# MachLoa.net
KiCad netlist of a schematic drawn in Altium Designer
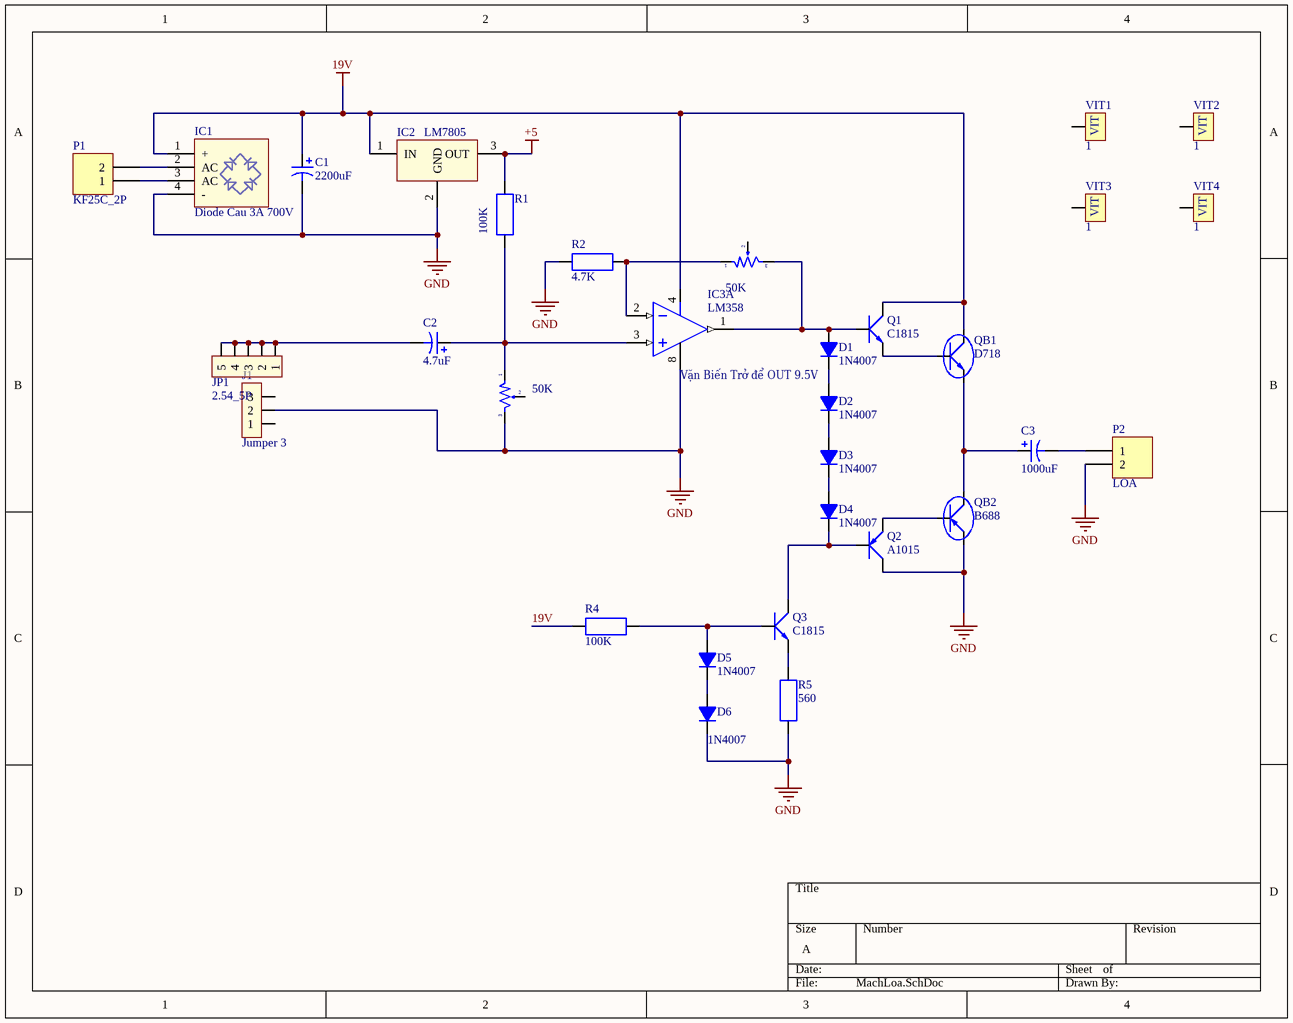
[diagram p0: MachLoa.SchDoc]

(export (version "E")
  (design (tool "Eeschema 10.0.6"))
  (components
    (comp (ref "C1")
      (value "2200uF")
      (footprint "C10mm")
      (description "Polarized Capacitor (Axial)")
      (fields (field (name "PUBLISHER") "Altium Limited"))
      (libsource (lib "NBBLib 14-03-2012") (part "Cap Pol 12mm"))
    )
    (comp (ref "C2")
      (value "4.7uF")
      (footprint "C10mm")
      (description "Polarized Capacitor (Axial)")
      (fields (field (name "PUBLISHER") "Altium Limited"))
      (libsource (lib "NBBLib 14-03-2012") (part "Cap Pol 12mm"))
    )
    (comp (ref "C3")
      (value "1000uF")
      (footprint "C10mm")
      (description "Polarized Capacitor (Axial)")
      (fields (field (name "PUBLISHER") "Altium Limited"))
      (libsource (lib "NBBLib 14-03-2012") (part "Cap Pol 12mm"))
    )
    (comp (ref "D1")
      (value "1N4007")
      (footprint "D1A")
      (description "Diode 1A")
      (libsource (lib "syhaunguyen") (part "D1A"))
    )
    (comp (ref "D2")
      (value "1N4007")
      (footprint "D1A")
      (description "Diode 1A")
      (libsource (lib "syhaunguyen") (part "D1A"))
    )
    (comp (ref "D3")
      (value "1N4007")
      (footprint "D1A")
      (description "Diode 1A")
      (libsource (lib "syhaunguyen") (part "D1A"))
    )
    (comp (ref "D4")
      (value "1N4007")
      (footprint "D1A")
      (description "Diode 1A")
      (libsource (lib "syhaunguyen") (part "D1A"))
    )
    (comp (ref "D5")
      (value "1N4007")
      (footprint "D1A")
      (description "Diode 1A")
      (libsource (lib "syhaunguyen") (part "D1A"))
    )
    (comp (ref "D6")
      (value "1N4007")
      (footprint "D1A")
      (description "Diode 1A")
      (libsource (lib "syhaunguyen") (part "D1A"))
    )
    (comp (ref "IC1")
      (value "Diode Cau 3A 700V")
      (footprint "diode cau")
      (description "Cắm")
      (libsource (lib "SCH Chuan") (part "Diode Cau 3A 700V"))
    )
    (comp (ref "IC2")
      (value "LM7805")
      (footprint "QTO-220H3")
      (description "On ap +, from + 5 to + 24VDC")
      (libsource (lib "syhaunguyen") (part "LM78xx"))
    )
    (comp (ref "IC3")
      (value "LM358")
      (footprint "DIP8/W0.3")
      (description "Low-Power Dual Operational Amplifier")
      (libsource (lib "syhaunguyen") (part "LM358"))
    )
    (comp (ref "J1") (value "Jumper 3") (footprint "JP3") (libsource (lib "syhaunguyen") (part "JP3")))
    (comp (ref "JP1")
      (value "2.54_5P")
      (footprint "jump don duc 2.54_5p")
      (description "Cắm")
      (libsource (lib "NhomLib") (part "Jump Don Duc 2.54_5P"))
    )
    (comp (ref "P1")
      (value "KF25C_2P")
      (footprint "KF25C_2P")
      (description "Header, 2-Pin, pitch 7.62mm")
      (libsource (lib "") (part "KF25C_2P_1"))
    )
    (comp (ref "P2")
      (value "LOA")
      (footprint "KF25C_2P")
      (description "Header, 2-Pin, pitch 7.62mm")
      (fields (field (name "MPN") "KF25C_2P"))
      (libsource (lib "BYTECH_HW_LIB_2019") (part "KF25C_2P"))
    )
    (comp (ref "Q1")
      (value "C1815")
      (footprint "QTO-92")
      (description "NPN 600mW, ECB")
      (libsource (lib "syhaunguyen") (part "C1815"))
    )
    (comp (ref "Q2")
      (value "A1015")
      (footprint "QTO-92")
      (description "PNP 600mW, ECB")
      (libsource (lib "syhaunguyen") (part "A1015"))
    )
    (comp (ref "Q3")
      (value "C1815")
      (footprint "QTO-92")
      (description "NPN 600mW, ECB")
      (libsource (lib "syhaunguyen") (part "C1815"))
    )
    (comp (ref "QB1")
      (value "D718")
      (footprint "QTO-247")
      (description "Transistor Power Supply")
      (libsource (lib "syhaunguyen") (part "D718"))
    )
    (comp (ref "QB2")
      (value "B688")
      (footprint "QTO-247")
      (description "Transistor Power Supply")
      (libsource (lib "syhaunguyen") (part "B688"))
    )
    (comp (ref "R1")
      (value "100K")
      (footprint "R2W")
      (description "Resistor 2W")
      (libsource (lib "syhaunguyen") (part "R2W"))
    )
    (comp (ref "R2")
      (value "4.7K")
      (footprint "R2W")
      (description "Resistor 2W")
      (libsource (lib "syhaunguyen") (part "R2W"))
    )
    (comp (ref "R4")
      (value "100K")
      (footprint "R2W")
      (description "Resistor 2W")
      (libsource (lib "syhaunguyen") (part "R2W"))
    )
    (comp (ref "R5")
      (value "560")
      (footprint "R2W")
      (description "Resistor 2W")
      (libsource (lib "syhaunguyen") (part "R2W"))
    )
    (comp (ref "VIT1")
      (value "1")
      (footprint "VIT")
      (description "Oc Vit")
      (libsource (lib "syhaunguyen") (part "VIT"))
    )
    (comp (ref "VIT2")
      (value "1")
      (footprint "VIT")
      (description "Oc Vit")
      (libsource (lib "syhaunguyen") (part "VIT"))
    )
    (comp (ref "VIT3")
      (value "1")
      (footprint "VIT")
      (description "Oc Vit")
      (libsource (lib "syhaunguyen") (part "VIT"))
    )
    (comp (ref "VIT4")
      (value "1")
      (footprint "VIT")
      (description "Oc Vit")
      (libsource (lib "syhaunguyen") (part "VIT"))
    )
    (comp (ref "Volum1")
      (value "50K")
      (footprint "BIEN TRO VI CHINH Dung")
      (description "Volume control Dual")
      (libsource (lib "syhaunguyen") (part "VOL-D"))
    )
    (comp (ref "Volum2")
      (value "50K")
      (footprint "VOL-D")
      (description "Volume control Dual")
      (libsource (lib "syhaunguyen") (part "VOL-D"))
    )
  )
  (nets
    (net (code "1") (name "+5") (class "Default")
      (node (ref "IC2") (pin "3") (pinfunction "OUT_3") (pintype "passive"))
      (node (ref "R1") (pin "2") (pinfunction "2_2") (pintype "passive"))
    )
    (net (code "2") (name "19V") (class "Default")
      (node (ref "C1") (pin "1") (pinfunction "1_1") (pintype "passive"))
      (node (ref "IC1") (pin "1") (pinfunction "+_1") (pintype "passive"))
      (node (ref "IC2") (pin "1") (pinfunction "IN_1") (pintype "passive"))
      (node (ref "IC3") (pin "4") (pinfunction "-V_4") (pintype "passive"))
      (node (ref "Q1") (pin "2") (pinfunction "C_2") (pintype "passive"))
      (node (ref "QB1") (pin "2") (pinfunction "C_2") (pintype "passive"))
      (node (ref "R4") (pin "2") (pinfunction "2_2") (pintype "passive"))
    )
    (net (code "3") (name "GND") (class "Default")
      (node (ref "C1") (pin "2") (pinfunction "2_2") (pintype "passive"))
      (node (ref "D6") (pin "2") (pinfunction "K_2") (pintype "passive"))
      (node (ref "IC1") (pin "4") (pinfunction "-_4") (pintype "passive"))
      (node (ref "IC2") (pin "2") (pinfunction "GND_2") (pintype "passive"))
      (node (ref "IC3") (pin "8") (pinfunction "+V_8") (pintype "passive"))
      (node (ref "J1") (pin "2") (pinfunction "2_2") (pintype "passive"))
      (node (ref "P2") (pin "2") (pinfunction "2_2") (pintype "passive"))
      (node (ref "Q2") (pin "2") (pinfunction "C_2") (pintype "passive"))
      (node (ref "QB2") (pin "3") (pinfunction "E_3") (pintype "passive"))
      (node (ref "R2") (pin "2") (pinfunction "2_2") (pintype "passive"))
      (node (ref "R5") (pin "2") (pinfunction "2_2") (pintype "passive"))
      (node (ref "Volum1") (pin "3") (pinfunction "3_3") (pintype "passive"))
    )
    (net (code "4") (name "Net-(C2-Pad2)") (class "Default")
      (node (ref "C2") (pin "2") (pinfunction "2_2") (pintype "passive"))
      (node (ref "JP1") (pin "1") (pinfunction "1_1") (pintype "passive"))
      (node (ref "JP1") (pin "2") (pinfunction "2_2") (pintype "passive"))
      (node (ref "JP1") (pin "3") (pinfunction "3_3") (pintype "passive"))
      (node (ref "JP1") (pin "4") (pinfunction "4_4") (pintype "passive"))
      (node (ref "JP1") (pin "5") (pinfunction "5_5") (pintype "passive"))
    )
    (net (code "5") (name "Net-(C3-Pad2)") (class "Default")
      (node (ref "C3") (pin "2") (pinfunction "2_2") (pintype "passive"))
      (node (ref "P2") (pin "1") (pinfunction "1_1") (pintype "passive"))
    )
    (net (code "6") (name "Net-(D1-A)") (class "Default")
      (node (ref "D1") (pin "1") (pinfunction "A_1") (pintype "passive"))
      (node (ref "IC3") (pin "1") (pinfunction "OUT_1") (pintype "output"))
      (node (ref "Q1") (pin "3") (pinfunction "B_3") (pintype "passive"))
      (node (ref "Volum2") (pin "3") (pinfunction "3_3") (pintype "passive"))
    )
    (net (code "7") (name "Net-(D1-K)") (class "Default")
      (node (ref "D1") (pin "2") (pinfunction "K_2") (pintype "passive"))
      (node (ref "D2") (pin "1") (pinfunction "A_1") (pintype "passive"))
    )
    (net (code "8") (name "Net-(D2-K)") (class "Default")
      (node (ref "D2") (pin "2") (pinfunction "K_2") (pintype "passive"))
      (node (ref "D3") (pin "1") (pinfunction "A_1") (pintype "passive"))
    )
    (net (code "9") (name "Net-(D3-K)") (class "Default")
      (node (ref "D3") (pin "2") (pinfunction "K_2") (pintype "passive"))
      (node (ref "D4") (pin "1") (pinfunction "A_1") (pintype "passive"))
    )
    (net (code "10") (name "Net-(D4-K)") (class "Default")
      (node (ref "D4") (pin "2") (pinfunction "K_2") (pintype "passive"))
      (node (ref "Q2") (pin "3") (pinfunction "B_3") (pintype "passive"))
      (node (ref "Q3") (pin "2") (pinfunction "C_2") (pintype "passive"))
    )
    (net (code "11") (name "Net-(D5-A)") (class "Default")
      (node (ref "D5") (pin "1") (pinfunction "A_1") (pintype "passive"))
      (node (ref "Q3") (pin "3") (pinfunction "B_3") (pintype "passive"))
      (node (ref "R4") (pin "1") (pinfunction "1_1") (pintype "passive"))
    )
    (net (code "12") (name "Net-(D5-K)") (class "Default")
      (node (ref "D5") (pin "2") (pinfunction "K_2") (pintype "passive"))
      (node (ref "D6") (pin "1") (pinfunction "A_1") (pintype "passive"))
    )
    (net (code "13") (name "Net-(IC1-AC-Pad2)") (class "Default")
      (node (ref "IC1") (pin "2") (pinfunction "AC_2") (pintype "passive"))
      (node (ref "P1") (pin "2") (pinfunction "2_2") (pintype "passive"))
    )
    (net (code "14") (name "Net-(IC1-AC-Pad3)") (class "Default")
      (node (ref "IC1") (pin "3") (pinfunction "AC_3") (pintype "passive"))
      (node (ref "P1") (pin "1") (pinfunction "1_1") (pintype "passive"))
    )
    (net (code "15") (name "Net-(IC3A-IN+)") (class "Default")
      (node (ref "C2") (pin "1") (pinfunction "1_1") (pintype "passive"))
      (node (ref "IC3") (pin "3") (pinfunction "IN+_3") (pintype "input"))
      (node (ref "R1") (pin "1") (pinfunction "1_1") (pintype "passive"))
      (node (ref "Volum1") (pin "1") (pinfunction "1_1") (pintype "passive"))
    )
    (net (code "16") (name "Net-(IC3A-IN-)") (class "Default")
      (node (ref "IC3") (pin "2") (pinfunction "IN-_2") (pintype "input"))
      (node (ref "R2") (pin "1") (pinfunction "1_1") (pintype "passive"))
      (node (ref "Volum2") (pin "1") (pinfunction "1_1") (pintype "passive"))
    )
    (net (code "17") (name "Net-(Q1-E)") (class "Default")
      (node (ref "Q1") (pin "1") (pinfunction "E_1") (pintype "passive"))
      (node (ref "QB1") (pin "1") (pinfunction "B_1") (pintype "passive"))
    )
    (net (code "18") (name "Net-(Q2-E)") (class "Default")
      (node (ref "Q2") (pin "1") (pinfunction "E_1") (pintype "passive"))
      (node (ref "QB2") (pin "1") (pinfunction "B_1") (pintype "passive"))
    )
    (net (code "19") (name "Net-(Q3-E)") (class "Default")
      (node (ref "Q3") (pin "1") (pinfunction "E_1") (pintype "passive"))
      (node (ref "R5") (pin "1") (pinfunction "1_1") (pintype "passive"))
    )
    (net (code "20") (name "Net-(QB1-E)") (class "Default")
      (node (ref "C3") (pin "1") (pinfunction "1_1") (pintype "passive"))
      (node (ref "QB1") (pin "3") (pinfunction "E_3") (pintype "passive"))
      (node (ref "QB2") (pin "2") (pinfunction "C_2") (pintype "passive"))
    )
    (net (code "21") (name "unconnected-(J1-Pad1)") (class "Default")
      (node (ref "J1") (pin "1") (pinfunction "1_1") (pintype "passive"))
    )
    (net (code "22") (name "unconnected-(J1-Pad3)") (class "Default")
      (node (ref "J1") (pin "3") (pinfunction "3_3") (pintype "passive"))
    )
    (net (code "23") (name "unconnected-(VIT1-1-PadVIT1)") (class "Default")
      (node (ref "VIT1") (pin "VIT1") (pinfunction "1_VIT1") (pintype "passive"))
    )
    (net (code "24") (name "unconnected-(VIT2-1-PadVIT1)") (class "Default")
      (node (ref "VIT2") (pin "VIT1") (pinfunction "1_VIT1") (pintype "passive"))
    )
    (net (code "25") (name "unconnected-(VIT3-1-PadVIT1)") (class "Default")
      (node (ref "VIT3") (pin "VIT1") (pinfunction "1_VIT1") (pintype "passive"))
    )
    (net (code "26") (name "unconnected-(VIT4-1-PadVIT1)") (class "Default")
      (node (ref "VIT4") (pin "VIT1") (pinfunction "1_VIT1") (pintype "passive"))
    )
    (net (code "27") (name "unconnected-(Volum1-Pad2)") (class "Default")
      (node (ref "Volum1") (pin "2") (pinfunction "2_2") (pintype "passive"))
    )
    (net (code "28") (name "unconnected-(Volum2-Pad2)") (class "Default")
      (node (ref "Volum2") (pin "2") (pinfunction "2_2") (pintype "passive"))
    )
  )
)
